# rgb_comm.net
KiCad netlist of a schematic drawn in EAGLE
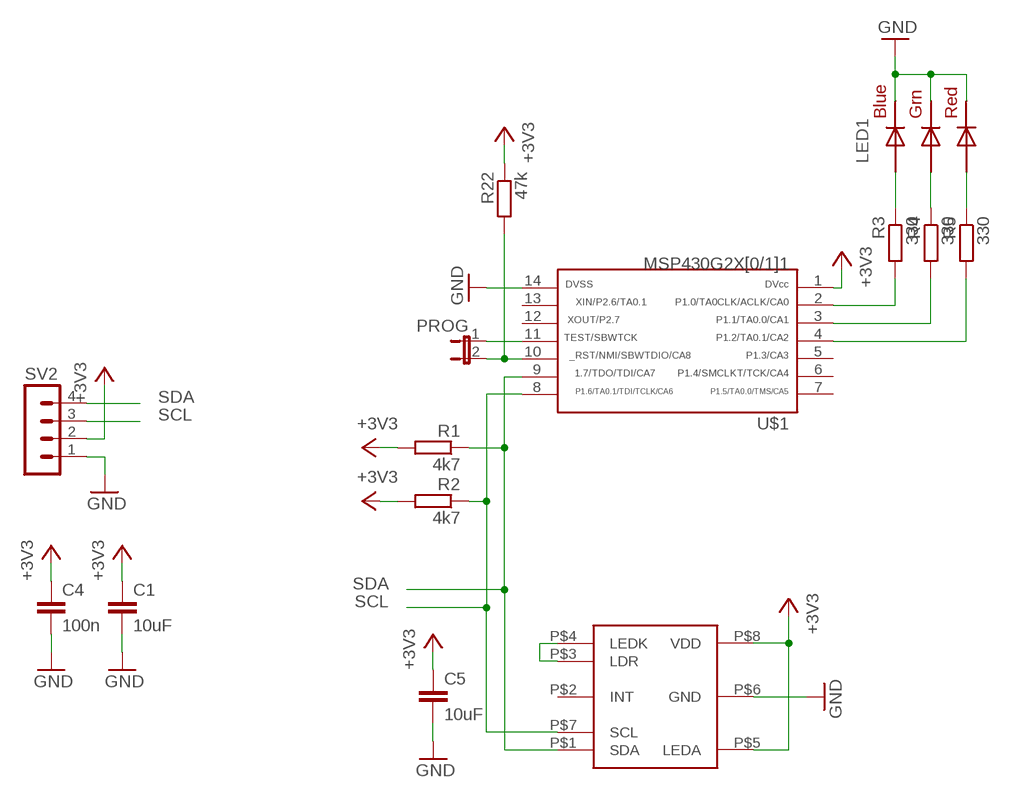
[diagram p0: schematic, sheet 1]

(export (version "E")
  (design (tool "Eeschema 10.0.6"))
  (components
    (comp (ref "C1")
      (value "10uF")
      (footprint "eagle-import:C0805")
      (libsource (lib "eagle-import") (part "C-EUC0805"))
    )
    (comp (ref "C4")
      (value "100n")
      (footprint "eagle-import:C0805")
      (libsource (lib "eagle-import") (part "C-EUC0805"))
    )
    (comp (ref "C5")
      (value "10uF")
      (footprint "eagle-import:C0805")
      (libsource (lib "eagle-import") (part "C-EUC0805"))
    )
    (comp (ref "LED1")
      (value "ADAFRUIT_RGBLED5050")
      (footprint "eagle-import:ADAFRUIT_RGBLED5050")
      (libsource (lib "eagle-import") (part "ADAFRUIT_RGBLED5050"))
    )
    (comp (ref "PROG")
      (value "JP1E")
      (footprint "eagle-import:JP1")
      (libsource (lib "eagle-import") (part "JP1E"))
    )
    (comp (ref "R1")
      (value "4k7")
      (footprint "eagle-import:M0805")
      (libsource (lib "eagle-import") (part "R-EU_M0805"))
    )
    (comp (ref "R2")
      (value "4k7")
      (footprint "eagle-import:M0805")
      (libsource (lib "eagle-import") (part "R-EU_M0805"))
    )
    (comp (ref "R3")
      (value "330")
      (footprint "eagle-import:M0805")
      (libsource (lib "eagle-import") (part "R-EU_M0805"))
    )
    (comp (ref "R4")
      (value "330")
      (footprint "eagle-import:M0805")
      (libsource (lib "eagle-import") (part "R-EU_M0805"))
    )
    (comp (ref "R5")
      (value "330")
      (footprint "eagle-import:M0805")
      (libsource (lib "eagle-import") (part "R-EU_M0805"))
    )
    (comp (ref "R22")
      (value "47k")
      (footprint "eagle-import:M0805")
      (libsource (lib "eagle-import") (part "R-EU_M0805"))
    )
    (comp (ref "SV2")
      (value "MA04-1")
      (footprint "eagle-import:MA04-1")
      (libsource (lib "eagle-import") (part "MA04-1"))
    )
    (comp (ref "U$1")
      (value "G2X[0/1]1---PW14")
      (footprint "eagle-import:PW14")
      (libsource (lib "eagle-import") (part "G2X[0/1]1---PW14"))
    )
    (comp (ref "U$2")
      (value "APDS9950")
      (footprint "eagle-import:APDS9950")
      (libsource (lib "eagle-import") (part "APDS9950"))
    )
  )
  (nets
    (net (code "1") (name "+3V3") (class "Default")
      (node (ref "C1") (pin "1") (pinfunction "1_1") (pintype "passive"))
      (node (ref "C4") (pin "1") (pinfunction "1_1") (pintype "passive"))
      (node (ref "C5") (pin "1") (pinfunction "1_1") (pintype "passive"))
      (node (ref "R1") (pin "2") (pinfunction "2_2") (pintype "passive"))
      (node (ref "R2") (pin "2") (pinfunction "2_2") (pintype "passive"))
      (node (ref "R22") (pin "1") (pinfunction "1_1") (pintype "passive"))
      (node (ref "SV2") (pin "2") (pinfunction "2_2") (pintype "passive"))
      (node (ref "U$1") (pin "1") (pinfunction "1_1") (pintype "bidirectional"))
      (node (ref "U$2") (pin "P$5") (pinfunction "LEDA_P$5") (pintype "bidirectional"))
      (node (ref "U$2") (pin "P$8") (pinfunction "VDD_P$8") (pintype "bidirectional"))
    )
    (net (code "2") (name "/SCL") (class "Default")
      (node (ref "R2") (pin "1") (pinfunction "1_1") (pintype "passive"))
      (node (ref "SV2") (pin "3") (pinfunction "3_3") (pintype "passive"))
      (node (ref "U$1") (pin "8") (pinfunction "8_8") (pintype "bidirectional"))
      (node (ref "U$2") (pin "P$7") (pinfunction "SCL_P$7") (pintype "bidirectional"))
    )
    (net (code "3") (name "/SDA") (class "Default")
      (node (ref "R1") (pin "1") (pinfunction "1_1") (pintype "passive"))
      (node (ref "SV2") (pin "4") (pinfunction "4_4") (pintype "passive"))
      (node (ref "U$1") (pin "9") (pinfunction "9_9") (pintype "bidirectional"))
      (node (ref "U$2") (pin "P$1") (pinfunction "SDA_P$1") (pintype "bidirectional"))
    )
    (net (code "4") (name "GND") (class "Default")
      (node (ref "C1") (pin "2") (pinfunction "2_2") (pintype "passive"))
      (node (ref "C4") (pin "2") (pinfunction "2_2") (pintype "passive"))
      (node (ref "C5") (pin "2") (pinfunction "2_2") (pintype "passive"))
      (node (ref "LED1") (pin "4") (pinfunction "BLUE_C_4") (pintype "bidirectional"))
      (node (ref "LED1") (pin "5") (pinfunction "RED_C_5") (pintype "bidirectional"))
      (node (ref "LED1") (pin "6") (pinfunction "GREEN_C_6") (pintype "bidirectional"))
      (node (ref "SV2") (pin "1") (pinfunction "1_1") (pintype "passive"))
      (node (ref "U$1") (pin "14") (pinfunction "14_14") (pintype "bidirectional"))
      (node (ref "U$2") (pin "P$6") (pinfunction "GND_P$6") (pintype "bidirectional"))
    )
    (net (code "5") (name "Net-(LED1-BLUE_A)") (class "Default")
      (node (ref "LED1") (pin "3") (pinfunction "BLUE_A_3") (pintype "bidirectional"))
      (node (ref "R3") (pin "1") (pinfunction "1_1") (pintype "passive"))
    )
    (net (code "6") (name "Net-(LED1-GREEN_A)") (class "Default")
      (node (ref "LED1") (pin "1") (pinfunction "GREEN_A_1") (pintype "bidirectional"))
      (node (ref "R4") (pin "1") (pinfunction "1_1") (pintype "passive"))
    )
    (net (code "7") (name "Net-(LED1-RED_A)") (class "Default")
      (node (ref "LED1") (pin "2") (pinfunction "RED_A_2") (pintype "bidirectional"))
      (node (ref "R5") (pin "1") (pinfunction "1_1") (pintype "passive"))
    )
    (net (code "8") (name "Net-(PROG-Pad1)") (class "Default")
      (node (ref "PROG") (pin "1") (pinfunction "1_1") (pintype "passive"))
      (node (ref "U$1") (pin "11") (pinfunction "11_11") (pintype "bidirectional"))
    )
    (net (code "9") (name "Net-(PROG-Pad2)") (class "Default")
      (node (ref "PROG") (pin "2") (pinfunction "2_2") (pintype "passive"))
      (node (ref "R22") (pin "2") (pinfunction "2_2") (pintype "passive"))
      (node (ref "U$1") (pin "10") (pinfunction "10_10") (pintype "bidirectional"))
    )
    (net (code "10") (name "Net-(R3-Pad2)") (class "Default")
      (node (ref "R3") (pin "2") (pinfunction "2_2") (pintype "passive"))
      (node (ref "U$1") (pin "2") (pinfunction "2_2") (pintype "bidirectional"))
    )
    (net (code "11") (name "Net-(R4-Pad2)") (class "Default")
      (node (ref "R4") (pin "2") (pinfunction "2_2") (pintype "passive"))
      (node (ref "U$1") (pin "3") (pinfunction "3_3") (pintype "bidirectional"))
    )
    (net (code "12") (name "Net-(R5-Pad2)") (class "Default")
      (node (ref "R5") (pin "2") (pinfunction "2_2") (pintype "passive"))
      (node (ref "U$1") (pin "4") (pinfunction "4_4") (pintype "bidirectional"))
    )
    (net (code "13") (name "Net-(U$2-LDR)") (class "Default")
      (node (ref "U$2") (pin "P$3") (pinfunction "LDR_P$3") (pintype "bidirectional"))
      (node (ref "U$2") (pin "P$4") (pinfunction "LEDK_P$4") (pintype "bidirectional"))
    )
    (net (code "14") (name "unconnected-(U$1-Pad5)") (class "Default")
      (node (ref "U$1") (pin "5") (pinfunction "5_5") (pintype "bidirectional"))
    )
    (net (code "15") (name "unconnected-(U$1-Pad6)") (class "Default")
      (node (ref "U$1") (pin "6") (pinfunction "6_6") (pintype "bidirectional"))
    )
    (net (code "16") (name "unconnected-(U$1-Pad7)") (class "Default")
      (node (ref "U$1") (pin "7") (pinfunction "7_7") (pintype "bidirectional"))
    )
    (net (code "17") (name "unconnected-(U$1-Pad12)") (class "Default")
      (node (ref "U$1") (pin "12") (pinfunction "12_12") (pintype "bidirectional"))
    )
    (net (code "18") (name "unconnected-(U$1-Pad13)") (class "Default")
      (node (ref "U$1") (pin "13") (pinfunction "13_13") (pintype "bidirectional"))
    )
    (net (code "19") (name "unconnected-(U$2-INT-PadP$2)") (class "Default")
      (node (ref "U$2") (pin "P$2") (pinfunction "INT_P$2") (pintype "bidirectional"))
    )
  )
)
